# MouseGoggles_HatBrd-1-1.net
KiCad netlist of a schematic drawn in EAGLE
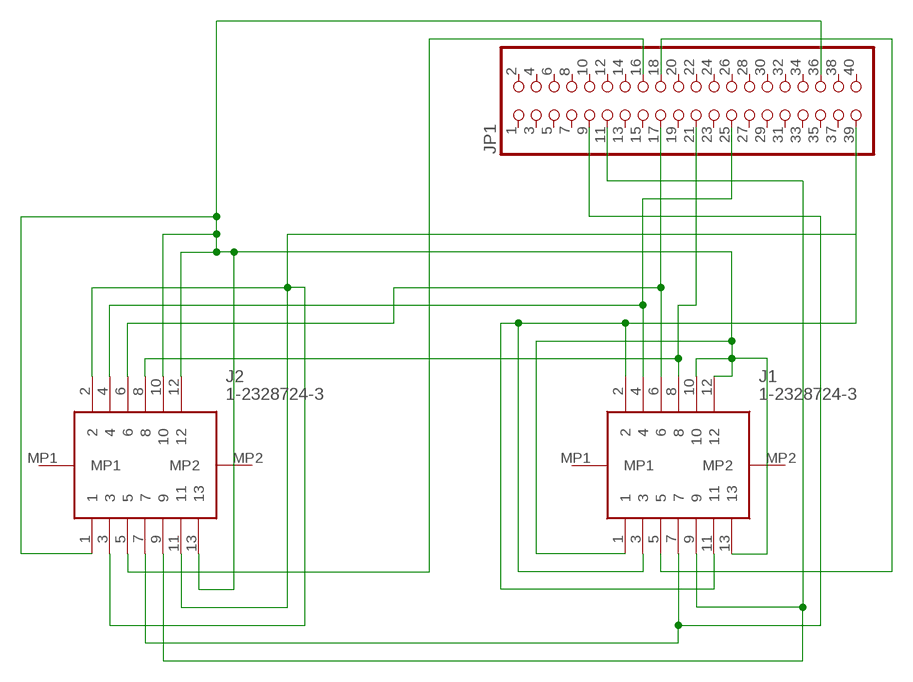
[diagram p0: schematic, sheet 1]

(export (version "E")
  (design (tool "Eeschema 10.0.6"))
  (components
    (comp (ref "J1")
      (value "1-2328724-3")
      (footprint "eagle-import:123287243")
      (fields (field (name "MOUSER_PART_NUMBER") "571-1-2328724-3"))
      (libsource (lib "eagle-import") (part "1-2328724-3"))
    )
    (comp (ref "J2")
      (value "1-2328724-3")
      (footprint "eagle-import:123287243")
      (fields (field (name "MOUSER_PART_NUMBER") "571-1-2328724-3"))
      (libsource (lib "eagle-import") (part "1-2328724-3"))
    )
    (comp (ref "JP1")
      (value "PINHD-2X20-BIG")
      (footprint "eagle-import:2X20-BIG")
      (libsource (lib "eagle-import") (part "PINHD-2X20-BIG"))
    )
  )
  (nets
    (net (code "1") (name "Net-(J1-Pad1)") (class "Default")
      (node (ref "J1") (pin "1") (pinfunction "1_1") (pintype "bidirectional"))
      (node (ref "J1") (pin "10") (pinfunction "10_10") (pintype "bidirectional"))
      (node (ref "J1") (pin "12") (pinfunction "12_12") (pintype "bidirectional"))
      (node (ref "J1") (pin "13") (pinfunction "13_13") (pintype "bidirectional"))
      (node (ref "J2") (pin "1") (pinfunction "1_1") (pintype "bidirectional"))
      (node (ref "J2") (pin "10") (pinfunction "10_10") (pintype "bidirectional"))
      (node (ref "J2") (pin "12") (pinfunction "12_12") (pintype "bidirectional"))
      (node (ref "J2") (pin "13") (pinfunction "13_13") (pintype "bidirectional"))
      (node (ref "JP1") (pin "36") (pinfunction "36_36") (pintype "passive"))
    )
    (net (code "2") (name "Net-(J1-Pad4)") (class "Default")
      (node (ref "J1") (pin "4") (pinfunction "4_4") (pintype "bidirectional"))
      (node (ref "J2") (pin "4") (pinfunction "4_4") (pintype "bidirectional"))
      (node (ref "JP1") (pin "25") (pinfunction "25_25") (pintype "passive"))
    )
    (net (code "3") (name "Net-(J1-Pad5)") (class "Default")
      (node (ref "J1") (pin "5") (pinfunction "5_5") (pintype "bidirectional"))
      (node (ref "JP1") (pin "18") (pinfunction "18_18") (pintype "passive"))
    )
    (net (code "4") (name "Net-(J1-Pad6)") (class "Default")
      (node (ref "J1") (pin "6") (pinfunction "6_6") (pintype "bidirectional"))
      (node (ref "J2") (pin "6") (pinfunction "6_6") (pintype "bidirectional"))
      (node (ref "JP1") (pin "17") (pinfunction "17_17") (pintype "passive"))
    )
    (net (code "5") (name "Net-(J1-Pad7)") (class "Default")
      (node (ref "J1") (pin "7") (pinfunction "7_7") (pintype "bidirectional"))
      (node (ref "J2") (pin "7") (pinfunction "7_7") (pintype "bidirectional"))
      (node (ref "JP1") (pin "9") (pinfunction "9_9") (pintype "passive"))
    )
    (net (code "6") (name "Net-(J1-Pad8)") (class "Default")
      (node (ref "J1") (pin "8") (pinfunction "8_8") (pintype "bidirectional"))
      (node (ref "J2") (pin "8") (pinfunction "8_8") (pintype "bidirectional"))
      (node (ref "JP1") (pin "21") (pinfunction "21_21") (pintype "passive"))
    )
    (net (code "7") (name "Net-(J1-Pad9)") (class "Default")
      (node (ref "J1") (pin "9") (pinfunction "9_9") (pintype "bidirectional"))
      (node (ref "J2") (pin "9") (pinfunction "9_9") (pintype "bidirectional"))
      (node (ref "JP1") (pin "11") (pinfunction "11_11") (pintype "passive"))
    )
    (net (code "8") (name "Net-(J1-Pad11)") (class "Default")
      (node (ref "J1") (pin "11") (pinfunction "11_11") (pintype "bidirectional"))
      (node (ref "J1") (pin "2") (pinfunction "2_2") (pintype "bidirectional"))
      (node (ref "J1") (pin "3") (pinfunction "3_3") (pintype "bidirectional"))
      (node (ref "J2") (pin "11") (pinfunction "11_11") (pintype "bidirectional"))
      (node (ref "J2") (pin "2") (pinfunction "2_2") (pintype "bidirectional"))
      (node (ref "J2") (pin "3") (pinfunction "3_3") (pintype "bidirectional"))
      (node (ref "JP1") (pin "39") (pinfunction "39_39") (pintype "passive"))
    )
    (net (code "9") (name "Net-(J2-Pad5)") (class "Default")
      (node (ref "J2") (pin "5") (pinfunction "5_5") (pintype "bidirectional"))
      (node (ref "JP1") (pin "16") (pinfunction "16_16") (pintype "passive"))
    )
    (net (code "10") (name "unconnected-(J1-PadMP1)") (class "Default")
      (node (ref "J1") (pin "MP1") (pinfunction "MP1_MP1") (pintype "bidirectional"))
    )
    (net (code "11") (name "unconnected-(J1-PadMP2)") (class "Default")
      (node (ref "J1") (pin "MP2") (pinfunction "MP2_MP2") (pintype "bidirectional"))
    )
    (net (code "12") (name "unconnected-(J2-PadMP1)") (class "Default")
      (node (ref "J2") (pin "MP1") (pinfunction "MP1_MP1") (pintype "bidirectional"))
    )
    (net (code "13") (name "unconnected-(J2-PadMP2)") (class "Default")
      (node (ref "J2") (pin "MP2") (pinfunction "MP2_MP2") (pintype "bidirectional"))
    )
    (net (code "14") (name "unconnected-(JP1-Pad1)") (class "Default")
      (node (ref "JP1") (pin "1") (pinfunction "1_1") (pintype "passive"))
    )
    (net (code "15") (name "unconnected-(JP1-Pad2)") (class "Default")
      (node (ref "JP1") (pin "2") (pinfunction "2_2") (pintype "passive"))
    )
    (net (code "16") (name "unconnected-(JP1-Pad3)") (class "Default")
      (node (ref "JP1") (pin "3") (pinfunction "3_3") (pintype "passive"))
    )
    (net (code "17") (name "unconnected-(JP1-Pad4)") (class "Default")
      (node (ref "JP1") (pin "4") (pinfunction "4_4") (pintype "passive"))
    )
    (net (code "18") (name "unconnected-(JP1-Pad5)") (class "Default")
      (node (ref "JP1") (pin "5") (pinfunction "5_5") (pintype "passive"))
    )
    (net (code "19") (name "unconnected-(JP1-Pad6)") (class "Default")
      (node (ref "JP1") (pin "6") (pinfunction "6_6") (pintype "passive"))
    )
    (net (code "20") (name "unconnected-(JP1-Pad7)") (class "Default")
      (node (ref "JP1") (pin "7") (pinfunction "7_7") (pintype "passive"))
    )
    (net (code "21") (name "unconnected-(JP1-Pad8)") (class "Default")
      (node (ref "JP1") (pin "8") (pinfunction "8_8") (pintype "passive"))
    )
    (net (code "22") (name "unconnected-(JP1-Pad10)") (class "Default")
      (node (ref "JP1") (pin "10") (pinfunction "10_10") (pintype "passive"))
    )
    (net (code "23") (name "unconnected-(JP1-Pad12)") (class "Default")
      (node (ref "JP1") (pin "12") (pinfunction "12_12") (pintype "passive"))
    )
    (net (code "24") (name "unconnected-(JP1-Pad13)") (class "Default")
      (node (ref "JP1") (pin "13") (pinfunction "13_13") (pintype "passive"))
    )
    (net (code "25") (name "unconnected-(JP1-Pad14)") (class "Default")
      (node (ref "JP1") (pin "14") (pinfunction "14_14") (pintype "passive"))
    )
    (net (code "26") (name "unconnected-(JP1-Pad15)") (class "Default")
      (node (ref "JP1") (pin "15") (pinfunction "15_15") (pintype "passive"))
    )
    (net (code "27") (name "unconnected-(JP1-Pad19)") (class "Default")
      (node (ref "JP1") (pin "19") (pinfunction "19_19") (pintype "passive"))
    )
    (net (code "28") (name "unconnected-(JP1-Pad20)") (class "Default")
      (node (ref "JP1") (pin "20") (pinfunction "20_20") (pintype "passive"))
    )
    (net (code "29") (name "unconnected-(JP1-Pad22)") (class "Default")
      (node (ref "JP1") (pin "22") (pinfunction "22_22") (pintype "passive"))
    )
    (net (code "30") (name "unconnected-(JP1-Pad23)") (class "Default")
      (node (ref "JP1") (pin "23") (pinfunction "23_23") (pintype "passive"))
    )
    (net (code "31") (name "unconnected-(JP1-Pad24)") (class "Default")
      (node (ref "JP1") (pin "24") (pinfunction "24_24") (pintype "passive"))
    )
    (net (code "32") (name "unconnected-(JP1-Pad26)") (class "Default")
      (node (ref "JP1") (pin "26") (pinfunction "26_26") (pintype "passive"))
    )
    (net (code "33") (name "unconnected-(JP1-Pad27)") (class "Default")
      (node (ref "JP1") (pin "27") (pinfunction "27_27") (pintype "passive"))
    )
    (net (code "34") (name "unconnected-(JP1-Pad28)") (class "Default")
      (node (ref "JP1") (pin "28") (pinfunction "28_28") (pintype "passive"))
    )
    (net (code "35") (name "unconnected-(JP1-Pad29)") (class "Default")
      (node (ref "JP1") (pin "29") (pinfunction "29_29") (pintype "passive"))
    )
    (net (code "36") (name "unconnected-(JP1-Pad30)") (class "Default")
      (node (ref "JP1") (pin "30") (pinfunction "30_30") (pintype "passive"))
    )
    (net (code "37") (name "unconnected-(JP1-Pad31)") (class "Default")
      (node (ref "JP1") (pin "31") (pinfunction "31_31") (pintype "passive"))
    )
    (net (code "38") (name "unconnected-(JP1-Pad32)") (class "Default")
      (node (ref "JP1") (pin "32") (pinfunction "32_32") (pintype "passive"))
    )
    (net (code "39") (name "unconnected-(JP1-Pad33)") (class "Default")
      (node (ref "JP1") (pin "33") (pinfunction "33_33") (pintype "passive"))
    )
    (net (code "40") (name "unconnected-(JP1-Pad34)") (class "Default")
      (node (ref "JP1") (pin "34") (pinfunction "34_34") (pintype "passive"))
    )
    (net (code "41") (name "unconnected-(JP1-Pad35)") (class "Default")
      (node (ref "JP1") (pin "35") (pinfunction "35_35") (pintype "passive"))
    )
    (net (code "42") (name "unconnected-(JP1-Pad37)") (class "Default")
      (node (ref "JP1") (pin "37") (pinfunction "37_37") (pintype "passive"))
    )
    (net (code "43") (name "unconnected-(JP1-Pad38)") (class "Default")
      (node (ref "JP1") (pin "38") (pinfunction "38_38") (pintype "passive"))
    )
    (net (code "44") (name "unconnected-(JP1-Pad40)") (class "Default")
      (node (ref "JP1") (pin "40") (pinfunction "40_40") (pintype "passive"))
    )
  )
)
